# 12V_Converter_3_6_2018.net
KiCad netlist of a schematic drawn in Altium Designer
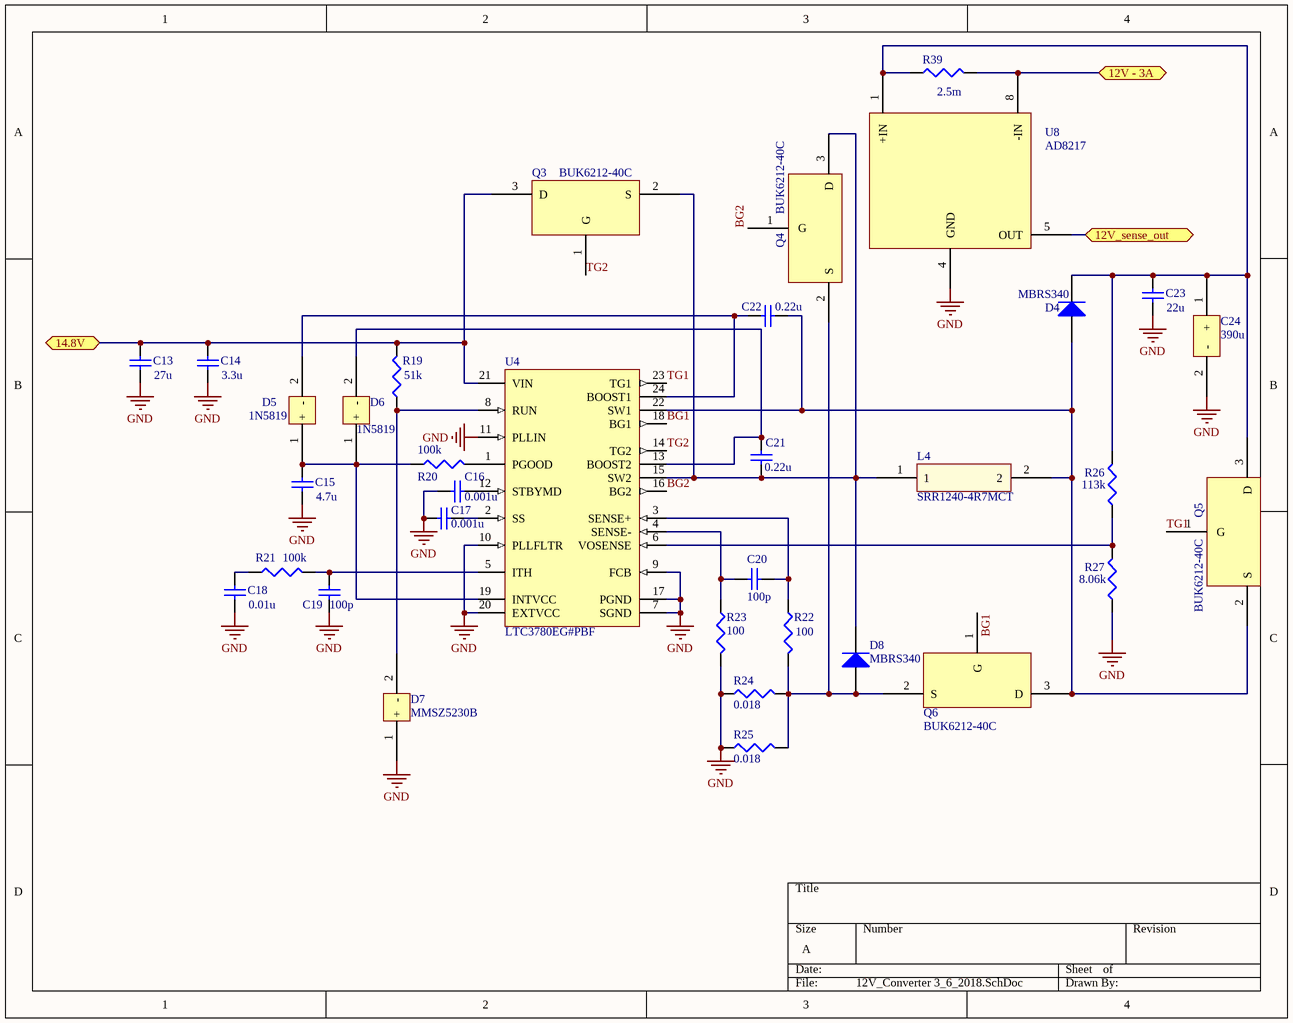
[diagram p0: 12V_Converter 3_6_2018.SchDoc]

(export (version "E")
  (design (tool "Eeschema 10.0.6"))
  (components
    (comp (ref "C13")
      (value "27u")
      (footprint "C1206")
      (description "Capacitor (Semiconductor SIM Model)")
      (fields (field (name "Comment") "Cap Semi") (field (name "PUBLISHER") "Altium Limited"))
      (libsource (lib "Miscellaneous Devices") (part "Cap Semi"))
    )
    (comp (ref "C14")
      (value "3.3u")
      (footprint "C1206")
      (description "Capacitor (Semiconductor SIM Model)")
      (fields (field (name "Comment") "Cap Semi") (field (name "PUBLISHER") "Altium Limited"))
      (libsource (lib "Miscellaneous Devices") (part "Cap Semi"))
    )
    (comp (ref "C15")
      (value "4.7u")
      (footprint "C1206")
      (description "Capacitor (Semiconductor SIM Model)")
      (fields (field (name "Comment") "Cap Semi") (field (name "PUBLISHER") "Altium Limited"))
      (libsource (lib "Miscellaneous Devices") (part "Cap Semi"))
    )
    (comp (ref "C16")
      (value "0.001u")
      (footprint "C1206")
      (description "Capacitor (Semiconductor SIM Model)")
      (fields (field (name "Comment") "Cap Semi") (field (name "PUBLISHER") "Altium Limited"))
      (libsource (lib "Miscellaneous Devices") (part "Cap Semi"))
    )
    (comp (ref "C17")
      (value "0.001u")
      (footprint "C1206")
      (description "Capacitor (Semiconductor SIM Model)")
      (fields (field (name "Comment") "Cap Semi") (field (name "PUBLISHER") "Altium Limited"))
      (libsource (lib "Miscellaneous Devices") (part "Cap Semi"))
    )
    (comp (ref "C18")
      (value "0.01u")
      (footprint "C1206")
      (description "Capacitor (Semiconductor SIM Model)")
      (fields (field (name "Comment") "Cap Semi") (field (name "PUBLISHER") "Altium Limited"))
      (libsource (lib "Miscellaneous Devices") (part "Cap Semi"))
    )
    (comp (ref "C19")
      (value "100p")
      (footprint "C1206")
      (description "Capacitor (Semiconductor SIM Model)")
      (fields (field (name "Comment") "Cap Semi") (field (name "PUBLISHER") "Altium Limited"))
      (libsource (lib "Miscellaneous Devices") (part "Cap Semi"))
    )
    (comp (ref "C20")
      (value "100p")
      (footprint "C1206")
      (description "Capacitor (Semiconductor SIM Model)")
      (fields (field (name "Comment") "Cap Semi") (field (name "PUBLISHER") "Altium Limited"))
      (libsource (lib "Miscellaneous Devices") (part "Cap Semi"))
    )
    (comp (ref "C21")
      (value "0.22u")
      (footprint "C1206")
      (description "Capacitor (Semiconductor SIM Model)")
      (fields (field (name "Comment") "Cap Semi") (field (name "PUBLISHER") "Altium Limited"))
      (libsource (lib "Miscellaneous Devices") (part "Cap Semi"))
    )
    (comp (ref "C22")
      (value "0.22u")
      (footprint "C1206")
      (description "Capacitor (Semiconductor SIM Model)")
      (fields (field (name "Comment") "Cap Semi") (field (name "PUBLISHER") "Altium Limited"))
      (libsource (lib "Miscellaneous Devices") (part "Cap Semi"))
    )
    (comp (ref "C23")
      (value "22u")
      (footprint "C1206")
      (description "Capacitor (Semiconductor SIM Model)")
      (fields (field (name "Comment") "Cap Semi") (field (name "PUBLISHER") "Altium Limited"))
      (libsource (lib "Miscellaneous Devices") (part "Cap Semi"))
    )
    (comp (ref "C24") (value "390u") (footprint "Alum_Cap") (libsource (lib "AluminumCap") (part "Alum_Cap")))
    (comp (ref "D4")
      (value "MBRS340")
      (footprint "SMC")
      (description "Default Diode")
      (fields (field (name "PUBLISHER") "Altium Limited"))
      (libsource (lib "Miscellaneous Devices") (part "Diode"))
    )
    (comp (ref "D5")
      (value "1N5819")
      (footprint "SOD-123")
      (libsource (lib "Diode (1N5819)") (part "Component_1"))
    )
    (comp (ref "D6")
      (value "1N5819")
      (footprint "SOD-123")
      (libsource (lib "Diode (1N5819)") (part "Component_1"))
    )
    (comp (ref "D7")
      (value "MMSZ5230B")
      (footprint "SOD-123")
      (libsource (lib "Diode (1N5819)") (part "Component_1"))
    )
    (comp (ref "D8")
      (value "MBRS340")
      (footprint "SMC")
      (description "Default Diode")
      (fields (field (name "PUBLISHER") "Altium Limited"))
      (libsource (lib "Miscellaneous Devices") (part "Diode"))
    )
    (comp (ref "L4")
      (value "SRR1240-4R7MCT")
      (footprint "INDP125125X45N")
      (libsource (lib "SRR1240-4R7MCT") (part "SRR1240-4R7MCT"))
    )
    (comp (ref "Q3")
      (value "BUK6212-40C")
      (footprint "SOT457P1000X238-3N")
      (libsource (lib "") (part "Component_1_1"))
    )
    (comp (ref "Q4")
      (value "BUK6212-40C")
      (footprint "SOT457P1000X238-3N")
      (libsource (lib "BUK6212-40C") (part "Component_1"))
    )
    (comp (ref "Q5")
      (value "BUK6212-40C")
      (footprint "SOT457P1000X238-3N")
      (libsource (lib "BUK6212-40C") (part "Component_1"))
    )
    (comp (ref "Q6")
      (value "BUK6212-40C")
      (footprint "SOT457P1000X238-3N")
      (libsource (lib "") (part "Component_1_2"))
    )
    (comp (ref "R19")
      (value "51k")
      (footprint "J1-0603")
      (description "Resistor")
      (fields (field (name "Comment") "Res3") (field (name "PUBLISHER") "Altium Limited"))
      (libsource (lib "Miscellaneous Devices") (part "Res3"))
    )
    (comp (ref "R20")
      (value "100k")
      (footprint "J1-0603")
      (description "Resistor")
      (fields (field (name "Comment") "Res3") (field (name "PUBLISHER") "Altium Limited"))
      (libsource (lib "Miscellaneous Devices") (part "Res3"))
    )
    (comp (ref "R21")
      (value "100k")
      (footprint "J1-0603")
      (description "Resistor")
      (fields (field (name "Comment") "Res3") (field (name "PUBLISHER") "Altium Limited"))
      (libsource (lib "Miscellaneous Devices") (part "Res3"))
    )
    (comp (ref "R22")
      (value "100")
      (footprint "J1-0603")
      (description "Resistor")
      (fields (field (name "Comment") "Res3") (field (name "PUBLISHER") "Altium Limited"))
      (libsource (lib "Miscellaneous Devices") (part "Res3"))
    )
    (comp (ref "R23")
      (value "100")
      (footprint "J1-0603")
      (description "Resistor")
      (fields (field (name "Comment") "Res3") (field (name "PUBLISHER") "Altium Limited"))
      (libsource (lib "Miscellaneous Devices") (part "Res3"))
    )
    (comp (ref "R24")
      (value "0.018")
      (footprint "J1-0603")
      (description "Resistor")
      (fields (field (name "Comment") "Res3") (field (name "PUBLISHER") "Altium Limited"))
      (libsource (lib "Miscellaneous Devices") (part "Res3"))
    )
    (comp (ref "R25")
      (value "0.018")
      (footprint "J1-0603")
      (description "Resistor")
      (fields (field (name "Comment") "Res3") (field (name "PUBLISHER") "Altium Limited"))
      (libsource (lib "Miscellaneous Devices") (part "Res3"))
    )
    (comp (ref "R26")
      (value "113k")
      (footprint "J1-0603")
      (description "Resistor")
      (fields (field (name "Comment") "Res3") (field (name "PUBLISHER") "Altium Limited"))
      (libsource (lib "Miscellaneous Devices") (part "Res3"))
    )
    (comp (ref "R27")
      (value "8.06k")
      (footprint "J1-0603")
      (description "Resistor")
      (fields (field (name "Comment") "Res3") (field (name "PUBLISHER") "Altium Limited"))
      (libsource (lib "Miscellaneous Devices") (part "Res3"))
    )
    (comp (ref "R39")
      (value "2.5m")
      (footprint "J1-0603")
      (description "Resistor")
      (fields (field (name "Comment") "Res3") (field (name "PUBLISHER") "Altium Limited"))
      (libsource (lib "Miscellaneous Devices") (part "Res3"))
    )
    (comp (ref "U4")
      (value "LTC3780EG#PBF")
      (footprint "LT-G-24_N")
      (fields (field (name "MANUFACTURER") "Linear Technology"))
      (libsource (lib "Linear Technology Power Management Switching Regulator LTC1174-LTC3901") (part "LTC3780EG#PBF"))
    )
    (comp (ref "U8")
      (value "AD8217")
      (footprint "TSOP65P490X110-8N")
      (description "Current Shunt Moniter")
      (libsource (lib "AD8217") (part "Component_1"))
    )
  )
  (nets
    (net (code "1") (name "/12V - 3A") (class "Default")
      (node (ref "R39") (pin "2") (pinfunction "2_2") (pintype "passive"))
      (node (ref "U8") (pin "8") (pinfunction "-IN_8") (pintype "passive"))
    )
    (net (code "2") (name "/12V_sense_out") (class "Default")
      (node (ref "U8") (pin "5") (pinfunction "OUT_5") (pintype "passive"))
    )
    (net (code "3") (name "/14.8V") (class "Default")
      (node (ref "C13") (pin "2") (pinfunction "2_2") (pintype "passive"))
      (node (ref "C14") (pin "2") (pinfunction "2_2") (pintype "passive"))
      (node (ref "Q3") (pin "3") (pinfunction "D_3") (pintype "passive"))
      (node (ref "R19") (pin "2") (pinfunction "2_2") (pintype "passive"))
      (node (ref "U4") (pin "21") (pinfunction "VIN_21") (pintype "power_in"))
    )
    (net (code "4") (name "/BG1") (class "Default")
      (node (ref "Q6") (pin "1") (pinfunction "G_1") (pintype "passive"))
      (node (ref "U4") (pin "18") (pinfunction "BG1_18") (pintype "output"))
    )
    (net (code "5") (name "/BG2") (class "Default")
      (node (ref "Q4") (pin "1") (pinfunction "G_1") (pintype "passive"))
      (node (ref "U4") (pin "16") (pinfunction "BG2_16") (pintype "output"))
    )
    (net (code "6") (name "/TG1") (class "Default")
      (node (ref "Q5") (pin "1") (pinfunction "G_1") (pintype "passive"))
      (node (ref "U4") (pin "23") (pinfunction "TG1_23") (pintype "output"))
    )
    (net (code "7") (name "/TG2") (class "Default")
      (node (ref "Q3") (pin "1") (pinfunction "G_1") (pintype "passive"))
      (node (ref "U4") (pin "14") (pinfunction "TG2_14") (pintype "output"))
    )
    (net (code "8") (name "GND") (class "Default")
      (node (ref "C13") (pin "1") (pinfunction "1_1") (pintype "passive"))
      (node (ref "C14") (pin "1") (pinfunction "1_1") (pintype "passive"))
      (node (ref "C15") (pin "1") (pinfunction "1_1") (pintype "passive"))
      (node (ref "C16") (pin "1") (pinfunction "1_1") (pintype "passive"))
      (node (ref "C17") (pin "1") (pinfunction "1_1") (pintype "passive"))
      (node (ref "C18") (pin "1") (pinfunction "1_1") (pintype "passive"))
      (node (ref "C19") (pin "1") (pinfunction "1_1") (pintype "passive"))
      (node (ref "C23") (pin "1") (pinfunction "1_1") (pintype "passive"))
      (node (ref "C24") (pin "2") (pinfunction "-_2") (pintype "passive"))
      (node (ref "D7") (pin "1") (pinfunction "+_1") (pintype "passive"))
      (node (ref "R23") (pin "2") (pinfunction "2_2") (pintype "passive"))
      (node (ref "R24") (pin "1") (pinfunction "1_1") (pintype "passive"))
      (node (ref "R25") (pin "1") (pinfunction "1_1") (pintype "passive"))
      (node (ref "R27") (pin "1") (pinfunction "1_1") (pintype "passive"))
      (node (ref "U4") (pin "10") (pinfunction "PLLFLTR_10") (pintype "input"))
      (node (ref "U4") (pin "11") (pinfunction "PLLIN_11") (pintype "input"))
      (node (ref "U4") (pin "17") (pinfunction "PGND_17") (pintype "power_in"))
      (node (ref "U4") (pin "20") (pinfunction "EXTVCC_20") (pintype "power_in"))
      (node (ref "U4") (pin "7") (pinfunction "SGND_7") (pintype "power_in"))
      (node (ref "U4") (pin "9") (pinfunction "FCB_9") (pintype "input"))
      (node (ref "U8") (pin "4") (pinfunction "GND_4") (pintype "passive"))
    )
    (net (code "9") (name "Net-(C18-Pad2)") (class "Default")
      (node (ref "C18") (pin "2") (pinfunction "2_2") (pintype "passive"))
      (node (ref "R21") (pin "1") (pinfunction "1_1") (pintype "passive"))
    )
    (net (code "10") (name "Net-(C24-+)") (class "Default")
      (node (ref "C23") (pin "2") (pinfunction "2_2") (pintype "passive"))
      (node (ref "C24") (pin "1") (pinfunction "+_1") (pintype "passive"))
      (node (ref "D4") (pin "2") (pinfunction "K_2") (pintype "passive"))
      (node (ref "Q5") (pin "3") (pinfunction "D_3") (pintype "passive"))
      (node (ref "R26") (pin "2") (pinfunction "2_2") (pintype "passive"))
      (node (ref "R39") (pin "1") (pinfunction "1_1") (pintype "passive"))
      (node (ref "U8") (pin "1") (pinfunction "+IN_1") (pintype "passive"))
    )
    (net (code "11") (name "Net-(D4-A)") (class "Default")
      (node (ref "C22") (pin "1") (pinfunction "1_1") (pintype "passive"))
      (node (ref "D4") (pin "1") (pinfunction "A_1") (pintype "passive"))
      (node (ref "L4") (pin "2") (pinfunction "2_2") (pintype "passive"))
      (node (ref "Q5") (pin "2") (pinfunction "S_2") (pintype "passive"))
      (node (ref "Q6") (pin "3") (pinfunction "D_3") (pintype "passive"))
      (node (ref "U4") (pin "22") (pinfunction "SW1_22") (pintype "passive"))
    )
    (net (code "12") (name "Net-(D5-+)") (class "Default")
      (node (ref "C15") (pin "2") (pinfunction "2_2") (pintype "passive"))
      (node (ref "D5") (pin "1") (pinfunction "+_1") (pintype "passive"))
      (node (ref "D6") (pin "1") (pinfunction "+_1") (pintype "passive"))
      (node (ref "R20") (pin "1") (pinfunction "1_1") (pintype "passive"))
      (node (ref "U4") (pin "19") (pinfunction "INTVCC_19") (pintype "power_in"))
    )
    (net (code "13") (name "Net-(D5--)") (class "Default")
      (node (ref "C22") (pin "2") (pinfunction "2_2") (pintype "passive"))
      (node (ref "D5") (pin "2") (pinfunction "-_2") (pintype "passive"))
      (node (ref "U4") (pin "24") (pinfunction "BOOST1_24") (pintype "passive"))
    )
    (net (code "14") (name "Net-(D6--)") (class "Default")
      (node (ref "C21") (pin "2") (pinfunction "2_2") (pintype "passive"))
      (node (ref "D6") (pin "2") (pinfunction "-_2") (pintype "passive"))
      (node (ref "U4") (pin "13") (pinfunction "BOOST2_13") (pintype "passive"))
    )
    (net (code "15") (name "Net-(D7--)") (class "Default")
      (node (ref "D7") (pin "2") (pinfunction "-_2") (pintype "passive"))
      (node (ref "R19") (pin "1") (pinfunction "1_1") (pintype "passive"))
      (node (ref "U4") (pin "8") (pinfunction "RUN_8") (pintype "input"))
    )
    (net (code "16") (name "Net-(D8-A)") (class "Default")
      (node (ref "D8") (pin "1") (pinfunction "A_1") (pintype "passive"))
      (node (ref "Q4") (pin "2") (pinfunction "S_2") (pintype "passive"))
      (node (ref "Q6") (pin "2") (pinfunction "S_2") (pintype "passive"))
      (node (ref "R22") (pin "2") (pinfunction "2_2") (pintype "passive"))
      (node (ref "R24") (pin "2") (pinfunction "2_2") (pintype "passive"))
      (node (ref "R25") (pin "2") (pinfunction "2_2") (pintype "passive"))
    )
    (net (code "17") (name "Net-(D8-K)") (class "Default")
      (node (ref "C21") (pin "1") (pinfunction "1_1") (pintype "passive"))
      (node (ref "D8") (pin "2") (pinfunction "K_2") (pintype "passive"))
      (node (ref "L4") (pin "1") (pinfunction "1_1") (pintype "passive"))
      (node (ref "Q3") (pin "2") (pinfunction "S_2") (pintype "passive"))
      (node (ref "Q4") (pin "3") (pinfunction "D_3") (pintype "passive"))
      (node (ref "U4") (pin "15") (pinfunction "SW2_15") (pintype "passive"))
    )
    (net (code "18") (name "Net-(U4-ITH)") (class "Default")
      (node (ref "C19") (pin "2") (pinfunction "2_2") (pintype "passive"))
      (node (ref "R21") (pin "2") (pinfunction "2_2") (pintype "passive"))
      (node (ref "U4") (pin "5") (pinfunction "ITH_5") (pintype "passive"))
    )
    (net (code "19") (name "Net-(U4-PGOOD)") (class "Default")
      (node (ref "R20") (pin "2") (pinfunction "2_2") (pintype "passive"))
      (node (ref "U4") (pin "1") (pinfunction "PGOOD_1") (pintype "open_collector"))
    )
    (net (code "20") (name "Net-(U4-SENSE+)") (class "Default")
      (node (ref "C20") (pin "2") (pinfunction "2_2") (pintype "passive"))
      (node (ref "R22") (pin "1") (pinfunction "1_1") (pintype "passive"))
      (node (ref "U4") (pin "3") (pinfunction "SENSE+_3") (pintype "input"))
    )
    (net (code "21") (name "Net-(U4-SENSE-)") (class "Default")
      (node (ref "C20") (pin "1") (pinfunction "1_1") (pintype "passive"))
      (node (ref "R23") (pin "1") (pinfunction "1_1") (pintype "passive"))
      (node (ref "U4") (pin "4") (pinfunction "SENSE-_4") (pintype "input"))
    )
    (net (code "22") (name "Net-(U4-SS)") (class "Default")
      (node (ref "C17") (pin "2") (pinfunction "2_2") (pintype "passive"))
      (node (ref "U4") (pin "2") (pinfunction "SS_2") (pintype "input"))
    )
    (net (code "23") (name "Net-(U4-STBYMD)") (class "Default")
      (node (ref "C16") (pin "2") (pinfunction "2_2") (pintype "passive"))
      (node (ref "U4") (pin "12") (pinfunction "STBYMD_12") (pintype "input"))
    )
    (net (code "24") (name "Net-(U4-VOSENSE)") (class "Default")
      (node (ref "R26") (pin "1") (pinfunction "1_1") (pintype "passive"))
      (node (ref "R27") (pin "2") (pinfunction "2_2") (pintype "passive"))
      (node (ref "U4") (pin "6") (pinfunction "VOSENSE_6") (pintype "input"))
    )
  )
)
